# Digital_to_Analog.net
KiCad netlist of a schematic drawn in Altium Designer
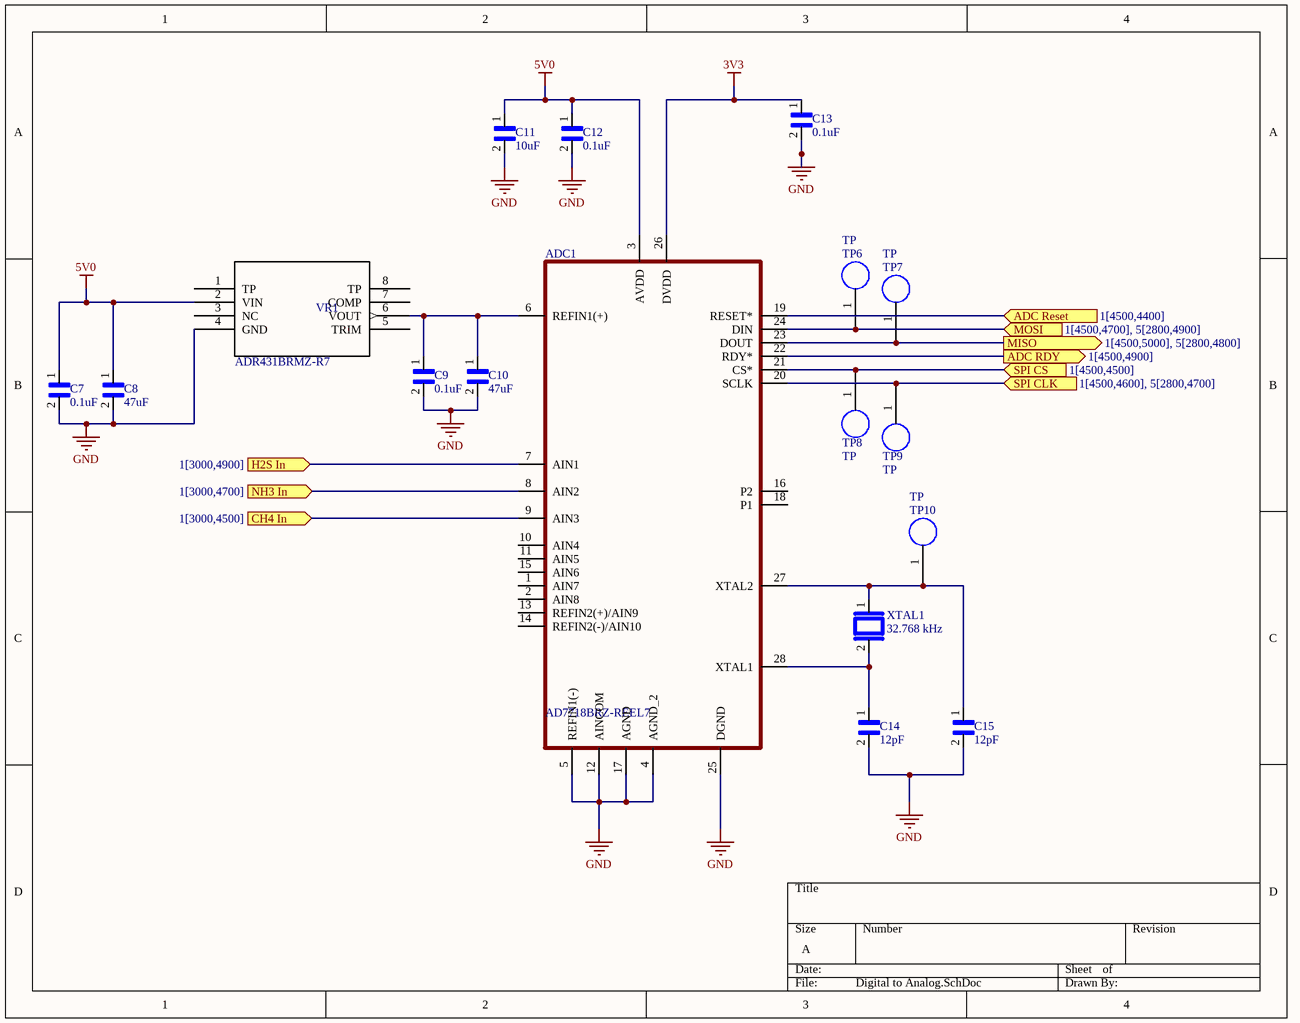
[diagram p0: Digital to Analog.SchDoc]

(export (version "E")
  (design (tool "Eeschema 10.0.6"))
  (components
    (comp (ref "ADC1")
      (value "AD7718BRZ-REEL7")
      (footprint "SOIC127P1032X265-28N")
      (description "24-Bit, 8/10-Channel, Low Voltage, Low Power, Sigma Delta ADC")
      (fields (field (name "MF") "Analog Devices"))
      (libsource (lib "AD7718") (part "AD7718BRZ-REEL7"))
    )
    (comp (ref "C7")
      (value "0.1uF")
      (footprint "0.1uF Capacitor")
      (description "No Description Available")
      (libsource (lib "0.1uF Capacitor") (part "CC1206JRX7R9BB104"))
    )
    (comp (ref "C8")
      (value "47uF")
      (footprint "47uF Capacitor:CAPC2012X135N")
      (description "47ÂµF Â±20% 6.3V Ceramic Capacitor X5R 0805 _2012 Metric_")
      (fields
        (field (name "MF") "Samsung Electro-Mechanics")
        (field (name "DIGI-KEY_PART_NUMBER") "1276-6467-1-ND")
      )
      (libsource (lib "47uF Capacitor") (part "CL21A476MQYNNNG"))
    )
    (comp (ref "C9")
      (value "0.1uF")
      (footprint "0.1uF Capacitor")
      (description "No Description Available")
      (libsource (lib "0.1uF Capacitor") (part "CC1206JRX7R9BB104"))
    )
    (comp (ref "C10")
      (value "47uF")
      (footprint "47uF Capacitor:CAPC2012X135N")
      (description "47ÂµF Â±20% 6.3V Ceramic Capacitor X5R 0805 _2012 Metric_")
      (fields
        (field (name "MF") "Samsung Electro-Mechanics")
        (field (name "DIGI-KEY_PART_NUMBER") "1276-6467-1-ND")
      )
      (libsource (lib "47uF Capacitor") (part "CL21A476MQYNNNG"))
    )
    (comp (ref "C11")
      (value "10uF")
      (footprint "10uF Capacitor:CAPC3216X190N")
      (description "CAP CER 10UF 25V X5R 1206")
      (fields (field (name "MP") "GRJ31CR61E106KE11L"))
      (libsource (lib "10uF Capacitor") (part "GRJ31CR61E106KE11L"))
    )
    (comp (ref "C12")
      (value "0.1uF")
      (footprint "0.1uF Capacitor")
      (description "No Description Available")
      (libsource (lib "0.1uF Capacitor") (part "CC1206JRX7R9BB104"))
    )
    (comp (ref "C13")
      (value "0.1uF")
      (footprint "0.1uF Capacitor")
      (description "No Description Available")
      (libsource (lib "0.1uF Capacitor") (part "CC1206JRX7R9BB104"))
    )
    (comp (ref "C14")
      (value "12pF")
      (footprint "CAPC1608X90N")
      (description "Multilayer Ceramic Capacitor, CGA Series, 12 pF, - 5%, C0G / NP0, 50 V, 0603 [1608 Metric]")
      (fields (field (name "MF") "TDK") (field (name "MP") "CGA3E2C0G1H120J080AA"))
      (libsource (lib "12pF Capacitor") (part "CGA3E2C0G1H120J080AA"))
    )
    (comp (ref "C15")
      (value "12pF")
      (footprint "CAPC1608X90N")
      (description "Multilayer Ceramic Capacitor, CGA Series, 12 pF, - 5%, C0G / NP0, 50 V, 0603 [1608 Metric]")
      (fields (field (name "MF") "TDK") (field (name "MP") "CGA3E2C0G1H120J080AA"))
      (libsource (lib "12pF Capacitor") (part "CGA3E2C0G1H120J080AA"))
    )
    (comp (ref "TP6")
      (value "TP")
      (footprint "TestPoint")
      (description "Test point for voltage, current, ect.")
      (libsource (lib "TestPoint") (part "TestPoint"))
    )
    (comp (ref "TP7")
      (value "TP")
      (footprint "TestPoint")
      (description "Test point for voltage, current, ect.")
      (libsource (lib "TestPoint") (part "TestPoint"))
    )
    (comp (ref "TP8")
      (value "TP")
      (footprint "TestPoint")
      (description "Test point for voltage, current, ect.")
      (libsource (lib "TestPoint") (part "TestPoint"))
    )
    (comp (ref "TP9")
      (value "TP")
      (footprint "TestPoint")
      (description "Test point for voltage, current, ect.")
      (libsource (lib "TestPoint") (part "TestPoint"))
    )
    (comp (ref "TP10")
      (value "TP")
      (footprint "TestPoint")
      (description "Test point for voltage, current, ect.")
      (libsource (lib "TestPoint") (part "TestPoint"))
    )
    (comp (ref "VR1")
      (value "ADR431BRMZ-R7")
      (footprint "RM_8_ADI")
      (description "No Description Available")
      (libsource (lib "Voltage Reference") (part "ADR431BRMZ-R7"))
    )
    (comp (ref "XTAL1")
      (value "32.768 kHz")
      (footprint "XTAL_ABS07-32.768KHZ-T")
      (description "32.768 kHz Â±20ppm Crystal 12.5pF 70 kOhms 2-SMD, No Lead")
      (fields (field (name "MP") "ABS07-32.768KHZ-T") (field (name "MF") "Abracon"))
      (libsource (lib "Watch Crystal") (part "ABS07-32.768KHZ-T"))
    )
  )
  (nets
    (net (code "1") (name "/ADC RDY") (class "Default")
      (node (ref "ADC1") (pin "22") (pinfunction "RDY*_22") (pintype "passive"))
    )
    (net (code "2") (name "/ADC Reset") (class "Default")
      (node (ref "ADC1") (pin "19") (pinfunction "RESET*_19") (pintype "passive"))
    )
    (net (code "3") (name "/CH4 In") (class "Default")
      (node (ref "ADC1") (pin "9") (pinfunction "AIN3_9") (pintype "passive"))
    )
    (net (code "4") (name "/H2S In") (class "Default")
      (node (ref "ADC1") (pin "7") (pinfunction "AIN1_7") (pintype "passive"))
    )
    (net (code "5") (name "/MISO") (class "Default")
      (node (ref "ADC1") (pin "23") (pinfunction "DOUT_23") (pintype "passive"))
      (node (ref "TP7") (pin "1") (pintype "passive"))
    )
    (net (code "6") (name "/MOSI") (class "Default")
      (node (ref "ADC1") (pin "24") (pinfunction "DIN_24") (pintype "passive"))
      (node (ref "TP6") (pin "1") (pintype "passive"))
    )
    (net (code "7") (name "/NH3 In") (class "Default")
      (node (ref "ADC1") (pin "8") (pinfunction "AIN2_8") (pintype "passive"))
    )
    (net (code "8") (name "/SPI CLK") (class "Default")
      (node (ref "ADC1") (pin "20") (pinfunction "SCLK_20") (pintype "passive"))
      (node (ref "TP9") (pin "1") (pintype "passive"))
    )
    (net (code "9") (name "/SPI CS") (class "Default")
      (node (ref "ADC1") (pin "21") (pinfunction "CS*_21") (pintype "passive"))
      (node (ref "TP8") (pin "1") (pintype "passive"))
    )
    (net (code "10") (name "3V3") (class "Default")
      (node (ref "ADC1") (pin "26") (pinfunction "DVDD_26") (pintype "power_in"))
      (node (ref "C13") (pin "1") (pintype "passive"))
    )
    (net (code "11") (name "5V0") (class "Default")
      (node (ref "ADC1") (pin "3") (pinfunction "AVDD_3") (pintype "power_in"))
      (node (ref "C11") (pin "1") (pinfunction "1_1") (pintype "passive"))
      (node (ref "C12") (pin "1") (pintype "passive"))
      (node (ref "C7") (pin "1") (pintype "passive"))
      (node (ref "C8") (pin "1") (pinfunction "1_1") (pintype "passive"))
      (node (ref "VR1") (pin "2") (pinfunction "VIN_2") (pintype "passive"))
    )
    (net (code "12") (name "GND") (class "Default")
      (node (ref "ADC1") (pin "12") (pinfunction "AINCOM_12") (pintype "passive"))
      (node (ref "ADC1") (pin "17") (pinfunction "AGND_17") (pintype "passive"))
      (node (ref "ADC1") (pin "25") (pinfunction "DGND_25") (pintype "passive"))
      (node (ref "ADC1") (pin "4") (pinfunction "AGND_2_4") (pintype "passive"))
      (node (ref "ADC1") (pin "5") (pinfunction "REFIN1(-)_5") (pintype "passive"))
      (node (ref "C10") (pin "2") (pinfunction "2_2") (pintype "passive"))
      (node (ref "C11") (pin "2") (pinfunction "2_2") (pintype "passive"))
      (node (ref "C12") (pin "2") (pintype "passive"))
      (node (ref "C13") (pin "2") (pintype "passive"))
      (node (ref "C14") (pin "2") (pintype "passive"))
      (node (ref "C15") (pin "2") (pintype "passive"))
      (node (ref "C7") (pin "2") (pintype "passive"))
      (node (ref "C8") (pin "2") (pinfunction "2_2") (pintype "passive"))
      (node (ref "C9") (pin "2") (pintype "passive"))
      (node (ref "VR1") (pin "4") (pinfunction "GND_4") (pintype "power_in"))
    )
    (net (code "13") (name "Net-(ADC1-REFIN1(+))") (class "Default")
      (node (ref "ADC1") (pin "6") (pinfunction "REFIN1(+)_6") (pintype "passive"))
      (node (ref "C10") (pin "1") (pinfunction "1_1") (pintype "passive"))
      (node (ref "C9") (pin "1") (pintype "passive"))
      (node (ref "VR1") (pin "6") (pinfunction "VOUT_6") (pintype "output"))
    )
    (net (code "14") (name "Net-(ADC1-XTAL1)") (class "Default")
      (node (ref "ADC1") (pin "28") (pinfunction "XTAL1_28") (pintype "passive"))
      (node (ref "C14") (pin "1") (pintype "passive"))
      (node (ref "XTAL1") (pin "2") (pinfunction "2_2") (pintype "passive"))
    )
    (net (code "15") (name "Net-(ADC1-XTAL2)") (class "Default")
      (node (ref "ADC1") (pin "27") (pinfunction "XTAL2_27") (pintype "passive"))
      (node (ref "C15") (pin "1") (pintype "passive"))
      (node (ref "TP10") (pin "1") (pintype "passive"))
      (node (ref "XTAL1") (pin "1") (pinfunction "1_1") (pintype "passive"))
    )
    (net (code "16") (name "unconnected-(ADC1-AIN4-Pad10)") (class "Default")
      (node (ref "ADC1") (pin "10") (pinfunction "AIN4_10") (pintype "passive"))
    )
    (net (code "17") (name "unconnected-(ADC1-AIN5-Pad11)") (class "Default")
      (node (ref "ADC1") (pin "11") (pinfunction "AIN5_11") (pintype "passive"))
    )
    (net (code "18") (name "unconnected-(ADC1-AIN6-Pad15)") (class "Default")
      (node (ref "ADC1") (pin "15") (pinfunction "AIN6_15") (pintype "passive"))
    )
    (net (code "19") (name "unconnected-(ADC1-AIN7-Pad1)") (class "Default")
      (node (ref "ADC1") (pin "1") (pinfunction "AIN7_1") (pintype "passive"))
    )
    (net (code "20") (name "unconnected-(ADC1-AIN8-Pad2)") (class "Default")
      (node (ref "ADC1") (pin "2") (pinfunction "AIN8_2") (pintype "passive"))
    )
    (net (code "21") (name "unconnected-(ADC1-P1-Pad18)") (class "Default")
      (node (ref "ADC1") (pin "18") (pinfunction "P1_18") (pintype "passive"))
    )
    (net (code "22") (name "unconnected-(ADC1-P2-Pad16)") (class "Default")
      (node (ref "ADC1") (pin "16") (pinfunction "P2_16") (pintype "passive"))
    )
    (net (code "23") (name "unconnected-(ADC1-REFIN2(+){slash}AIN9-Pad13)") (class "Default")
      (node (ref "ADC1") (pin "13") (pinfunction "REFIN2(+)/AIN9_13") (pintype "passive"))
    )
    (net (code "24") (name "unconnected-(ADC1-REFIN2(-){slash}AIN10-Pad14)") (class "Default")
      (node (ref "ADC1") (pin "14") (pinfunction "REFIN2(-)/AIN10_14") (pintype "passive"))
    )
    (net (code "25") (name "unconnected-(VR1-COMP-Pad7)") (class "Default")
      (node (ref "VR1") (pin "7") (pinfunction "COMP_7") (pintype "passive"))
    )
    (net (code "26") (name "unconnected-(VR1-NC-Pad3)") (class "Default")
      (node (ref "VR1") (pin "3") (pinfunction "NC_3") (pintype "passive"))
    )
    (net (code "27") (name "unconnected-(VR1-TP-Pad1)") (class "Default")
      (node (ref "VR1") (pin "1") (pinfunction "TP_1") (pintype "passive"))
    )
    (net (code "28") (name "unconnected-(VR1-TP-Pad8)") (class "Default")
      (node (ref "VR1") (pin "8") (pinfunction "TP_8") (pintype "passive"))
    )
    (net (code "29") (name "unconnected-(VR1-TRIM-Pad5)") (class "Default")
      (node (ref "VR1") (pin "5") (pinfunction "TRIM_5") (pintype "passive"))
    )
  )
)
